# SchematicEdwarda.net
KiCad netlist of a schematic drawn in Altium Designer
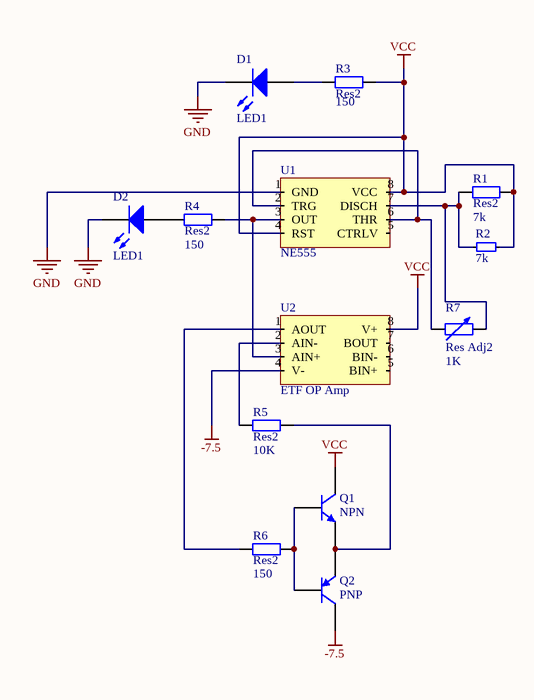
[diagram p0: SchematicEdwarda.SchDoc]

(export (version "E")
  (design (tool "Eeschema 10.0.6"))
  (components
    (comp (ref "D1")
      (value "LED1")
      (footprint "LED-1")
      (description "Typical RED GaAs LED")
      (fields (field (name "PUBLISHER") "Altium Limited"))
      (libsource (lib "Miscellaneous Devices") (part "LED1"))
    )
    (comp (ref "D2")
      (value "LED1")
      (footprint "LED-1")
      (description "Typical RED GaAs LED")
      (fields (field (name "PUBLISHER") "Altium Limited"))
      (libsource (lib "Miscellaneous Devices") (part "LED1"))
    )
    (comp (ref "Q1")
      (value "NPN")
      (footprint "TO-226-AA")
      (description "NPN Bipolar Transistor")
      (fields (field (name "PUBLISHER") "Altium Limited"))
      (libsource (lib "Miscellaneous Devices") (part "NPN"))
    )
    (comp (ref "Q2")
      (value "PNP")
      (footprint "SOT-23B_N")
      (description "PNP Bipolar Transistor")
      (fields (field (name "PUBLISHER") "Altium Limited"))
      (libsource (lib "Miscellaneous Devices") (part "PNP"))
    )
    (comp (ref "R1")
      (value "Res2")
      (footprint "AXIAL-0.4")
      (description "Resistor")
      (fields (field (name "ALTIUM_VALUE") "7k") (field (name "PUBLISHER") "Altium Limited"))
      (libsource (lib "Miscellaneous Devices") (part "Res2"))
    )
    (comp (ref "R2")
      (value "7k")
      (footprint "0603")
      (fields (field (name "Comment") "0402, resistor"))
      (libsource (lib "jclib") (part "0402, resistor"))
    )
    (comp (ref "R3")
      (value "Res2")
      (footprint "AXIAL-0.4")
      (description "Resistor")
      (fields (field (name "ALTIUM_VALUE") "150") (field (name "PUBLISHER") "Altium Limited"))
      (libsource (lib "Miscellaneous Devices") (part "Res2"))
    )
    (comp (ref "R4")
      (value "Res2")
      (footprint "AXIAL-0.4")
      (description "Resistor")
      (fields (field (name "ALTIUM_VALUE") "150") (field (name "PUBLISHER") "Altium Limited"))
      (libsource (lib "Miscellaneous Devices") (part "Res2"))
    )
    (comp (ref "R5")
      (value "Res2")
      (footprint "AXIAL-0.4")
      (description "Resistor")
      (fields (field (name "ALTIUM_VALUE") "10K") (field (name "PUBLISHER") "Altium Limited"))
      (libsource (lib "Miscellaneous Devices") (part "Res2"))
    )
    (comp (ref "R6")
      (value "Res2")
      (footprint "AXIAL-0.4")
      (description "Resistor")
      (fields (field (name "ALTIUM_VALUE") "150") (field (name "PUBLISHER") "Altium Limited"))
      (libsource (lib "Miscellaneous Devices") (part "Res2"))
    )
    (comp (ref "R7")
      (value "Res Adj2")
      (footprint "AXIAL-0.6")
      (description "Variable Resistor")
      (fields (field (name "ALTIUM_VALUE") "1K") (field (name "PUBLISHER") "Altium Limited"))
      (libsource (lib "Miscellaneous Devices") (part "Res Adj2"))
    )
    (comp (ref "U1")
      (value "NE555")
      (footprint "NE555")
      (libsource (lib "myIntegratedLibrary1") (part "NE555"))
    )
    (comp (ref "U2")
      (value "ETF OP Amp")
      (footprint "NE555")
      (libsource (lib "myIntegratedLibrary1") (part "TL082CP"))
    )
  )
  (nets
    (net (code "1") (name "-7.5") (class "Default")
      (node (ref "Q2") (pin "1") (pinfunction "C_1") (pintype "passive"))
      (node (ref "U2") (pin "4") (pinfunction "V-_4") (pintype "passive"))
    )
    (net (code "2") (name "GND") (class "Default")
      (node (ref "D1") (pin "2") (pinfunction "K_2") (pintype "passive"))
      (node (ref "D2") (pin "2") (pinfunction "K_2") (pintype "passive"))
      (node (ref "U1") (pin "1") (pinfunction "GND_1") (pintype "passive"))
    )
    (net (code "3") (name "Net-(D1-A)") (class "Default")
      (node (ref "D1") (pin "1") (pinfunction "A_1") (pintype "passive"))
      (node (ref "R3") (pin "1") (pinfunction "1_1") (pintype "passive"))
    )
    (net (code "4") (name "Net-(D2-A)") (class "Default")
      (node (ref "D2") (pin "1") (pinfunction "A_1") (pintype "passive"))
      (node (ref "R4") (pin "1") (pinfunction "1_1") (pintype "passive"))
    )
    (net (code "5") (name "Net-(Q1-B)") (class "Default")
      (node (ref "Q1") (pin "2") (pinfunction "B_2") (pintype "passive"))
      (node (ref "Q2") (pin "2") (pinfunction "B_2") (pintype "passive"))
      (node (ref "R6") (pin "2") (pinfunction "2_2") (pintype "passive"))
    )
    (net (code "6") (name "Net-(Q1-E)") (class "Default")
      (node (ref "Q1") (pin "3") (pinfunction "E_3") (pintype "passive"))
      (node (ref "Q2") (pin "3") (pinfunction "E_3") (pintype "passive"))
      (node (ref "R5") (pin "2") (pinfunction "2_2") (pintype "passive"))
    )
    (net (code "7") (name "Net-(U1-DISCH)") (class "Default")
      (node (ref "R1") (pin "1") (pinfunction "1_1") (pintype "passive"))
      (node (ref "R2") (pin "1") (pinfunction "1_1") (pintype "passive"))
      (node (ref "R7") (pin "2") (pinfunction "2_2") (pintype "passive"))
      (node (ref "U1") (pin "7") (pinfunction "DISCH_7") (pintype "passive"))
    )
    (net (code "8") (name "Net-(U1-OUT)") (class "Default")
      (node (ref "R4") (pin "2") (pinfunction "2_2") (pintype "passive"))
      (node (ref "U1") (pin "3") (pinfunction "OUT_3") (pintype "passive"))
      (node (ref "U2") (pin "3") (pinfunction "AIN+_3") (pintype "passive"))
    )
    (net (code "9") (name "Net-(U1-THR)") (class "Default")
      (node (ref "R7") (pin "1") (pinfunction "1_1") (pintype "passive"))
      (node (ref "U1") (pin "2") (pinfunction "TRG_2") (pintype "passive"))
      (node (ref "U1") (pin "6") (pinfunction "THR_6") (pintype "passive"))
    )
    (net (code "10") (name "Net-(U2-AIN-)") (class "Default")
      (node (ref "R5") (pin "1") (pinfunction "1_1") (pintype "passive"))
      (node (ref "U2") (pin "2") (pinfunction "AIN-_2") (pintype "passive"))
    )
    (net (code "11") (name "Net-(U2-AOUT)") (class "Default")
      (node (ref "R6") (pin "1") (pinfunction "1_1") (pintype "passive"))
      (node (ref "U2") (pin "1") (pinfunction "AOUT_1") (pintype "passive"))
    )
    (net (code "12") (name "VCC") (class "Default")
      (node (ref "Q1") (pin "1") (pinfunction "C_1") (pintype "passive"))
      (node (ref "R1") (pin "2") (pinfunction "2_2") (pintype "passive"))
      (node (ref "R2") (pin "0") (pinfunction "0_0") (pintype "passive"))
      (node (ref "R3") (pin "2") (pinfunction "2_2") (pintype "passive"))
      (node (ref "U1") (pin "4") (pinfunction "RST_4") (pintype "passive"))
      (node (ref "U1") (pin "8") (pinfunction "VCC_8") (pintype "passive"))
      (node (ref "U2") (pin "8") (pinfunction "V+_8") (pintype "passive"))
    )
    (net (code "13") (name "unconnected-(U1-CTRLV-Pad5)") (class "Default")
      (node (ref "U1") (pin "5") (pinfunction "CTRLV_5") (pintype "passive"))
    )
    (net (code "14") (name "unconnected-(U2-BIN+-Pad5)") (class "Default")
      (node (ref "U2") (pin "5") (pinfunction "BIN+_5") (pintype "passive"))
    )
    (net (code "15") (name "unconnected-(U2-BIN--Pad6)") (class "Default")
      (node (ref "U2") (pin "6") (pinfunction "BIN-_6") (pintype "passive"))
    )
    (net (code "16") (name "unconnected-(U2-BOUT-Pad7)") (class "Default")
      (node (ref "U2") (pin "7") (pinfunction "BOUT_7") (pintype "passive"))
    )
  )
)
